# Module_Output_Sockets.net
KiCad netlist of a schematic drawn in Altium Designer
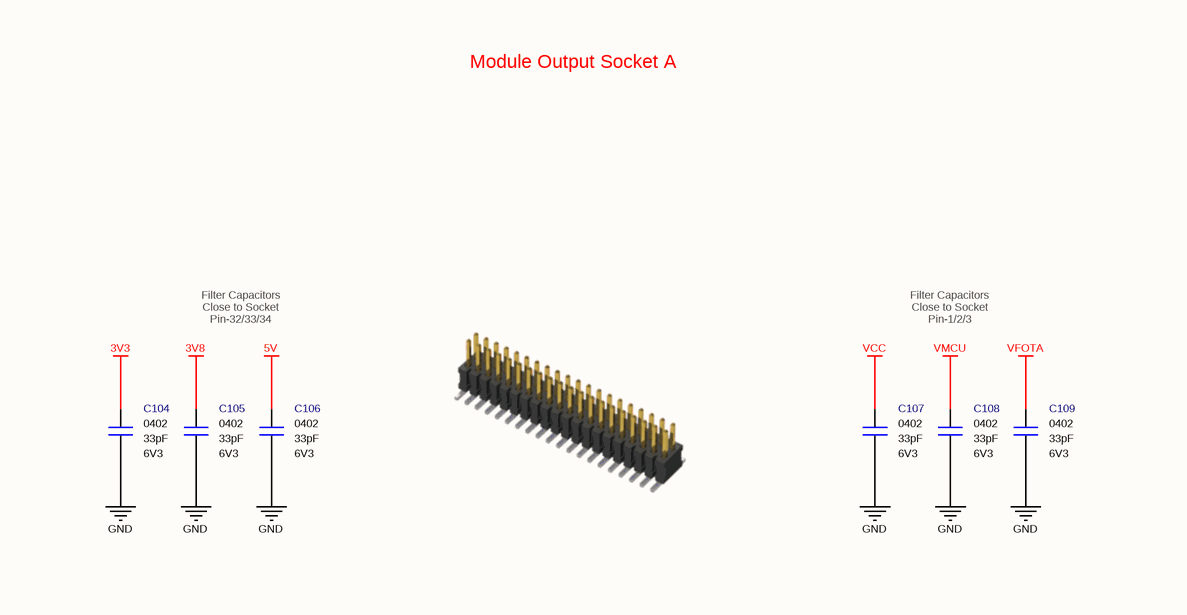
[diagram p0: Module Output Sockets.SchDoc, top left]
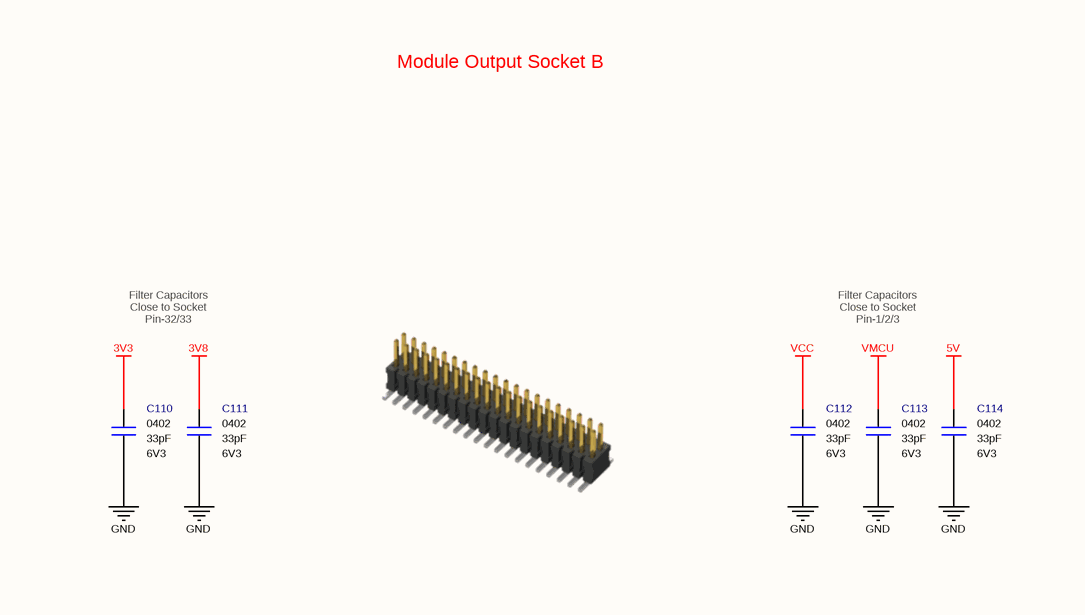
[diagram p1: Module Output Sockets.SchDoc, top right]
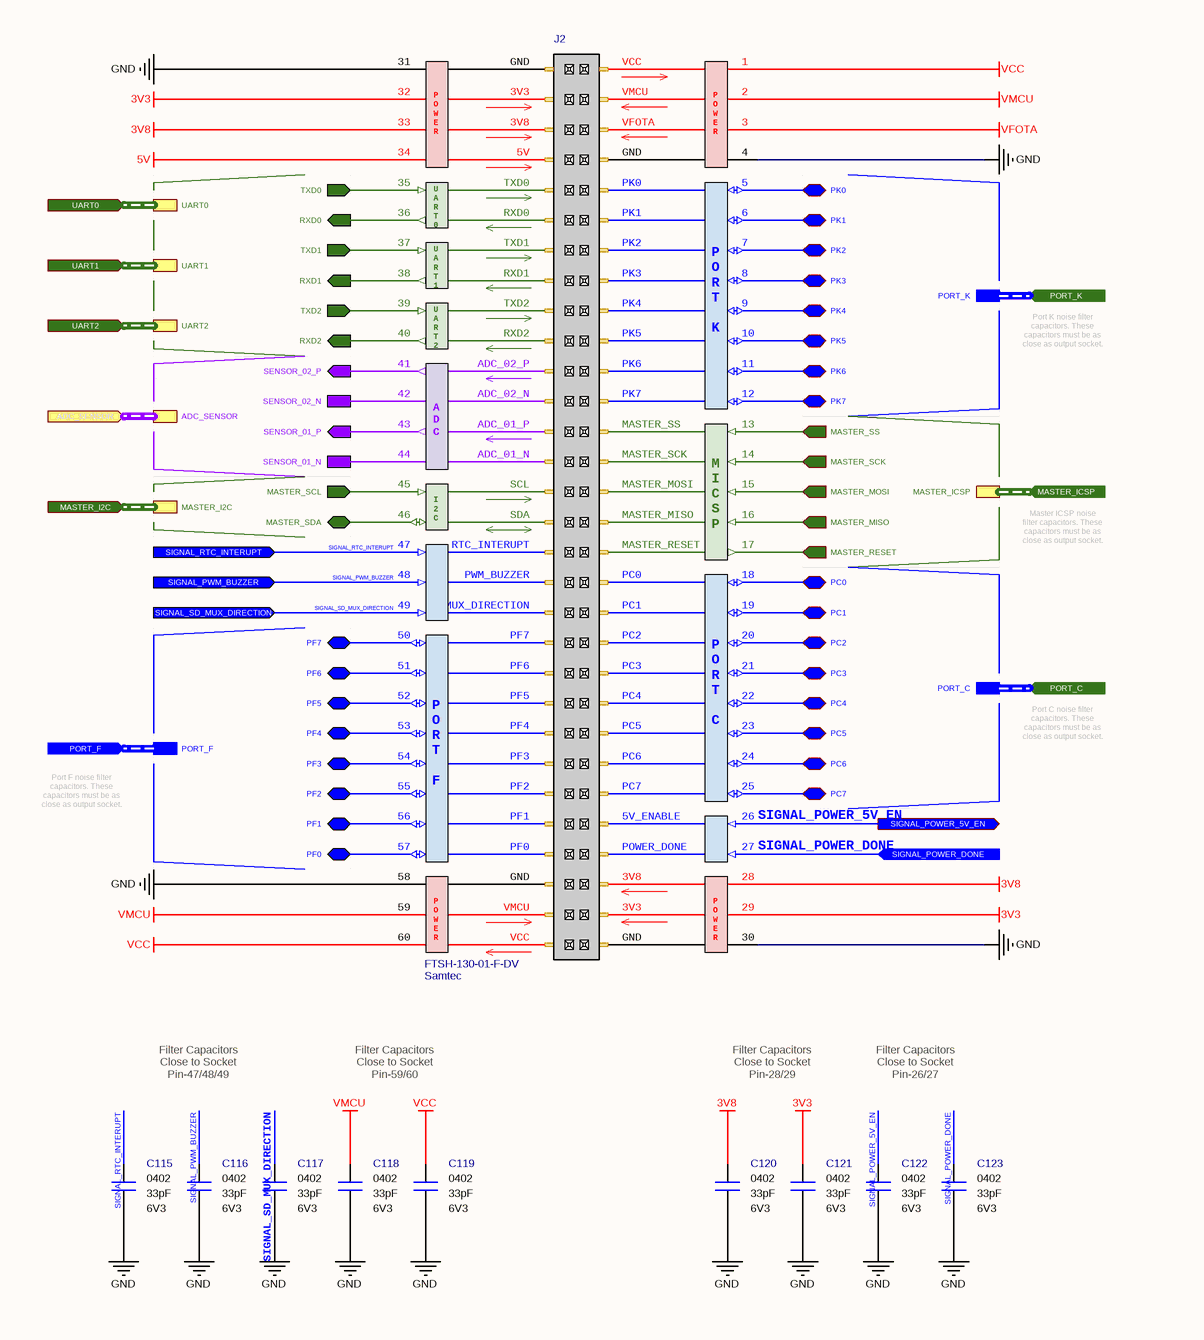
[diagram p2: Module Output Sockets.SchDoc, bottom left]
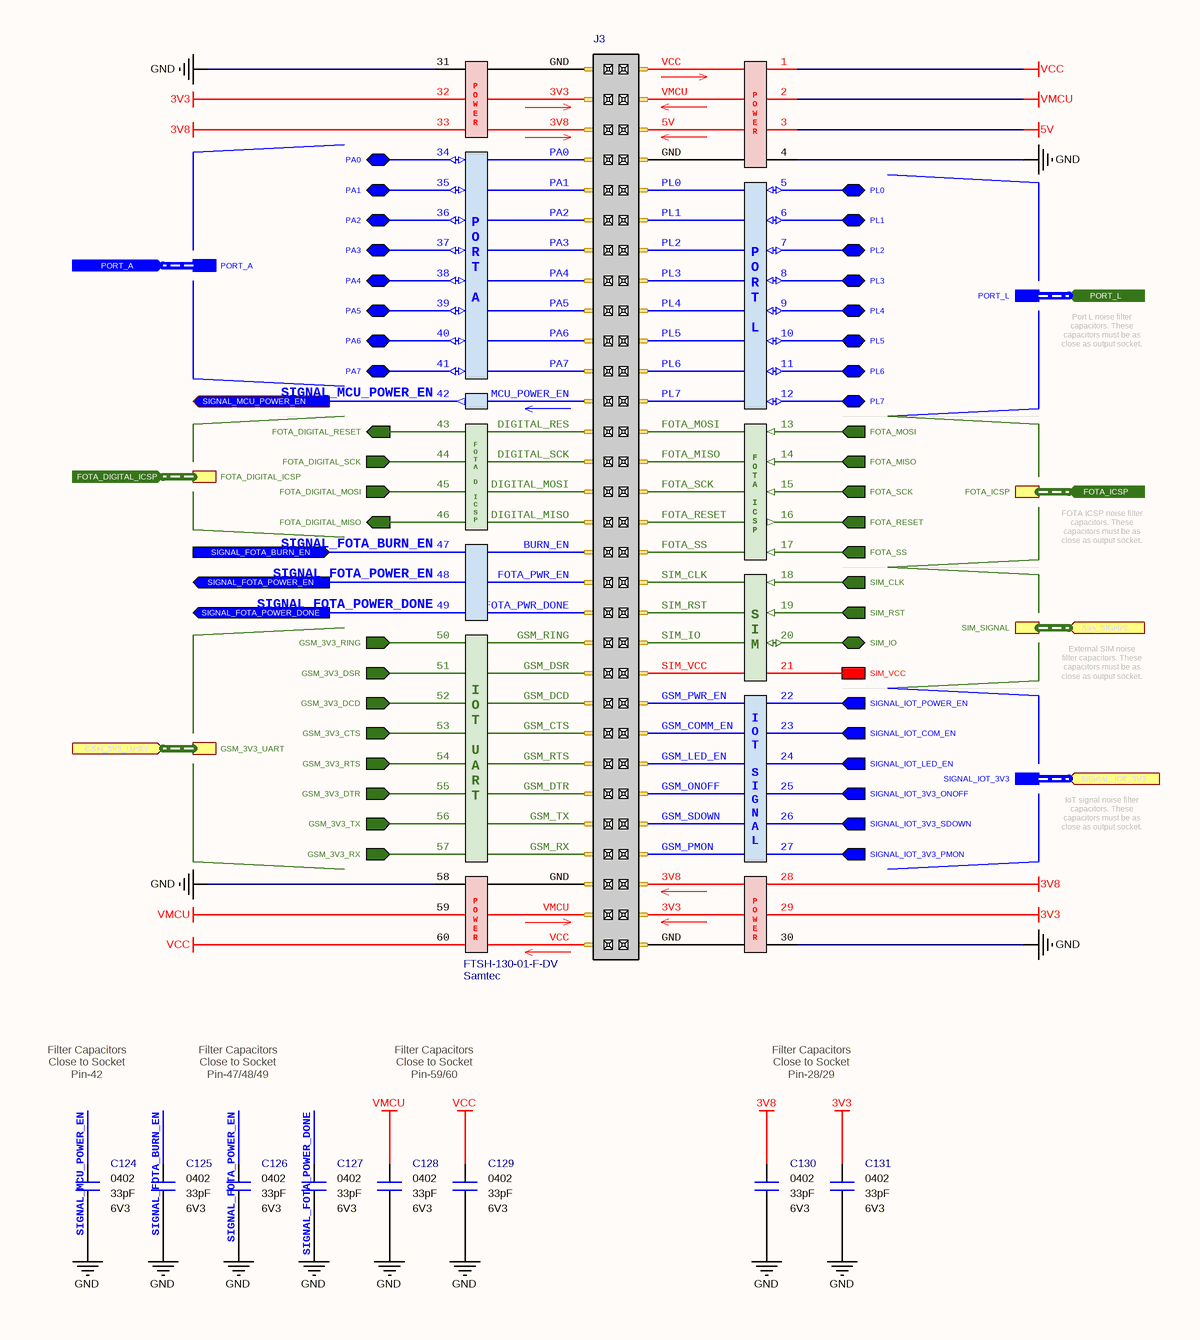
[diagram p3: Module Output Sockets.SchDoc, bottom right]

(export (version "E")
  (design (tool "Eeschema 10.0.6"))
  (components
    (comp (ref "C104")
      (value "33pF")
      (footprint "CAPACITOR_0402")
      (description "Capacitor - 33pF [0402] (Ceramic)")
      (fields
        (field (name "TOLERANCE") "10%")
        (field (name "CASE") "0402")
        (field (name "VOLTAGE") "6V3")
        (field (name "MANUFACTURER PART NUMBER") "C0402C330J9RACAUTO")
      )
      (libsource (lib "Ovoo_Library") (part "Capacitor - 33pF [0402-6V3]"))
    )
    (comp (ref "C105")
      (value "33pF")
      (footprint "CAPACITOR_0402")
      (description "Capacitor - 33pF [0402] (Ceramic)")
      (fields
        (field (name "TOLERANCE") "10%")
        (field (name "CASE") "0402")
        (field (name "VOLTAGE") "6V3")
        (field (name "MANUFACTURER PART NUMBER") "C0402C330J9RACAUTO")
      )
      (libsource (lib "Ovoo_Library") (part "Capacitor - 33pF [0402-6V3]"))
    )
    (comp (ref "C106")
      (value "33pF")
      (footprint "CAPACITOR_0402")
      (description "Capacitor - 33pF [0402] (Ceramic)")
      (fields
        (field (name "TOLERANCE") "10%")
        (field (name "CASE") "0402")
        (field (name "VOLTAGE") "6V3")
        (field (name "MANUFACTURER PART NUMBER") "C0402C330J9RACAUTO")
      )
      (libsource (lib "Ovoo_Library") (part "Capacitor - 33pF [0402-6V3]"))
    )
    (comp (ref "C107")
      (value "33pF")
      (footprint "CAPACITOR_0402")
      (description "Capacitor - 33pF [0402] (Ceramic)")
      (fields
        (field (name "TOLERANCE") "10%")
        (field (name "CASE") "0402")
        (field (name "VOLTAGE") "6V3")
        (field (name "MANUFACTURER PART NUMBER") "C0402C330J9RACAUTO")
      )
      (libsource (lib "Ovoo_Library") (part "Capacitor - 33pF [0402-6V3]"))
    )
    (comp (ref "C108")
      (value "33pF")
      (footprint "CAPACITOR_0402")
      (description "Capacitor - 33pF [0402] (Ceramic)")
      (fields
        (field (name "TOLERANCE") "10%")
        (field (name "CASE") "0402")
        (field (name "VOLTAGE") "6V3")
        (field (name "MANUFACTURER PART NUMBER") "C0402C330J9RACAUTO")
      )
      (libsource (lib "Ovoo_Library") (part "Capacitor - 33pF [0402-6V3]"))
    )
    (comp (ref "C109")
      (value "33pF")
      (footprint "CAPACITOR_0402")
      (description "Capacitor - 33pF [0402] (Ceramic)")
      (fields
        (field (name "TOLERANCE") "10%")
        (field (name "CASE") "0402")
        (field (name "VOLTAGE") "6V3")
        (field (name "MANUFACTURER PART NUMBER") "C0402C330J9RACAUTO")
      )
      (libsource (lib "Ovoo_Library") (part "Capacitor - 33pF [0402-6V3]"))
    )
    (comp (ref "C110")
      (value "33pF")
      (footprint "CAPACITOR_0402")
      (description "Capacitor - 33pF [0402] (Ceramic)")
      (fields
        (field (name "TOLERANCE") "10%")
        (field (name "CASE") "0402")
        (field (name "VOLTAGE") "6V3")
        (field (name "MANUFACTURER PART NUMBER") "C0402C330J9RACAUTO")
      )
      (libsource (lib "Ovoo_Library") (part "Capacitor - 33pF [0402-6V3]"))
    )
    (comp (ref "C111")
      (value "33pF")
      (footprint "CAPACITOR_0402")
      (description "Capacitor - 33pF [0402] (Ceramic)")
      (fields
        (field (name "TOLERANCE") "10%")
        (field (name "CASE") "0402")
        (field (name "VOLTAGE") "6V3")
        (field (name "MANUFACTURER PART NUMBER") "C0402C330J9RACAUTO")
      )
      (libsource (lib "Ovoo_Library") (part "Capacitor - 33pF [0402-6V3]"))
    )
    (comp (ref "C112")
      (value "33pF")
      (footprint "CAPACITOR_0402")
      (description "Capacitor - 33pF [0402] (Ceramic)")
      (fields
        (field (name "TOLERANCE") "10%")
        (field (name "CASE") "0402")
        (field (name "VOLTAGE") "6V3")
        (field (name "MANUFACTURER PART NUMBER") "C0402C330J9RACAUTO")
      )
      (libsource (lib "Ovoo_Library") (part "Capacitor - 33pF [0402-6V3]"))
    )
    (comp (ref "C113")
      (value "33pF")
      (footprint "CAPACITOR_0402")
      (description "Capacitor - 33pF [0402] (Ceramic)")
      (fields
        (field (name "TOLERANCE") "10%")
        (field (name "CASE") "0402")
        (field (name "VOLTAGE") "6V3")
        (field (name "MANUFACTURER PART NUMBER") "C0402C330J9RACAUTO")
      )
      (libsource (lib "Ovoo_Library") (part "Capacitor - 33pF [0402-6V3]"))
    )
    (comp (ref "C114")
      (value "33pF")
      (footprint "CAPACITOR_0402")
      (description "Capacitor - 33pF [0402] (Ceramic)")
      (fields
        (field (name "TOLERANCE") "10%")
        (field (name "CASE") "0402")
        (field (name "VOLTAGE") "6V3")
        (field (name "MANUFACTURER PART NUMBER") "C0402C330J9RACAUTO")
      )
      (libsource (lib "Ovoo_Library") (part "Capacitor - 33pF [0402-6V3]"))
    )
    (comp (ref "C115")
      (value "33pF")
      (footprint "CAPACITOR_0402")
      (description "Capacitor - 33pF [0402] (Ceramic)")
      (fields
        (field (name "TOLERANCE") "10%")
        (field (name "CASE") "0402")
        (field (name "VOLTAGE") "6V3")
        (field (name "MANUFACTURER PART NUMBER") "C0402C330J9RACAUTO")
      )
      (libsource (lib "Ovoo_Library") (part "Capacitor - 33pF [0402-6V3]"))
    )
    (comp (ref "C116")
      (value "33pF")
      (footprint "CAPACITOR_0402")
      (description "Capacitor - 33pF [0402] (Ceramic)")
      (fields
        (field (name "TOLERANCE") "10%")
        (field (name "CASE") "0402")
        (field (name "VOLTAGE") "6V3")
        (field (name "MANUFACTURER PART NUMBER") "C0402C330J9RACAUTO")
      )
      (libsource (lib "Ovoo_Library") (part "Capacitor - 33pF [0402-6V3]"))
    )
    (comp (ref "C117")
      (value "33pF")
      (footprint "CAPACITOR_0402")
      (description "Capacitor - 33pF [0402] (Ceramic)")
      (fields
        (field (name "TOLERANCE") "10%")
        (field (name "CASE") "0402")
        (field (name "VOLTAGE") "6V3")
        (field (name "MANUFACTURER PART NUMBER") "C0402C330J9RACAUTO")
      )
      (libsource (lib "Ovoo_Library") (part "Capacitor - 33pF [0402-6V3]"))
    )
    (comp (ref "C118")
      (value "33pF")
      (footprint "CAPACITOR_0402")
      (description "Capacitor - 33pF [0402] (Ceramic)")
      (fields
        (field (name "TOLERANCE") "10%")
        (field (name "CASE") "0402")
        (field (name "VOLTAGE") "6V3")
        (field (name "MANUFACTURER PART NUMBER") "C0402C330J9RACAUTO")
      )
      (libsource (lib "Ovoo_Library") (part "Capacitor - 33pF [0402-6V3]"))
    )
    (comp (ref "C119")
      (value "33pF")
      (footprint "CAPACITOR_0402")
      (description "Capacitor - 33pF [0402] (Ceramic)")
      (fields
        (field (name "TOLERANCE") "10%")
        (field (name "CASE") "0402")
        (field (name "VOLTAGE") "6V3")
        (field (name "MANUFACTURER PART NUMBER") "C0402C330J9RACAUTO")
      )
      (libsource (lib "Ovoo_Library") (part "Capacitor - 33pF [0402-6V3]"))
    )
    (comp (ref "C120")
      (value "33pF")
      (footprint "CAPACITOR_0402")
      (description "Capacitor - 33pF [0402] (Ceramic)")
      (fields
        (field (name "TOLERANCE") "10%")
        (field (name "CASE") "0402")
        (field (name "VOLTAGE") "6V3")
        (field (name "MANUFACTURER PART NUMBER") "C0402C330J9RACAUTO")
      )
      (libsource (lib "Ovoo_Library") (part "Capacitor - 33pF [0402-6V3]"))
    )
    (comp (ref "C121")
      (value "33pF")
      (footprint "CAPACITOR_0402")
      (description "Capacitor - 33pF [0402] (Ceramic)")
      (fields
        (field (name "TOLERANCE") "10%")
        (field (name "CASE") "0402")
        (field (name "VOLTAGE") "6V3")
        (field (name "MANUFACTURER PART NUMBER") "C0402C330J9RACAUTO")
      )
      (libsource (lib "Ovoo_Library") (part "Capacitor - 33pF [0402-6V3]"))
    )
    (comp (ref "C122")
      (value "33pF")
      (footprint "CAPACITOR_0402")
      (description "Capacitor - 33pF [0402] (Ceramic)")
      (fields
        (field (name "TOLERANCE") "10%")
        (field (name "CASE") "0402")
        (field (name "VOLTAGE") "6V3")
        (field (name "MANUFACTURER PART NUMBER") "C0402C330J9RACAUTO")
      )
      (libsource (lib "Ovoo_Library") (part "Capacitor - 33pF [0402-6V3]"))
    )
    (comp (ref "C123")
      (value "33pF")
      (footprint "CAPACITOR_0402")
      (description "Capacitor - 33pF [0402] (Ceramic)")
      (fields
        (field (name "TOLERANCE") "10%")
        (field (name "CASE") "0402")
        (field (name "VOLTAGE") "6V3")
        (field (name "MANUFACTURER PART NUMBER") "C0402C330J9RACAUTO")
      )
      (libsource (lib "Ovoo_Library") (part "Capacitor - 33pF [0402-6V3]"))
    )
    (comp (ref "C124")
      (value "33pF")
      (footprint "CAPACITOR_0402")
      (description "Capacitor - 33pF [0402] (Ceramic)")
      (fields
        (field (name "TOLERANCE") "10%")
        (field (name "CASE") "0402")
        (field (name "VOLTAGE") "6V3")
        (field (name "MANUFACTURER PART NUMBER") "C0402C330J9RACAUTO")
      )
      (libsource (lib "Ovoo_Library") (part "Capacitor - 33pF [0402-6V3]"))
    )
    (comp (ref "C125")
      (value "33pF")
      (footprint "CAPACITOR_0402")
      (description "Capacitor - 33pF [0402] (Ceramic)")
      (fields
        (field (name "TOLERANCE") "10%")
        (field (name "CASE") "0402")
        (field (name "VOLTAGE") "6V3")
        (field (name "MANUFACTURER PART NUMBER") "C0402C330J9RACAUTO")
      )
      (libsource (lib "Ovoo_Library") (part "Capacitor - 33pF [0402-6V3]"))
    )
    (comp (ref "C126")
      (value "33pF")
      (footprint "CAPACITOR_0402")
      (description "Capacitor - 33pF [0402] (Ceramic)")
      (fields
        (field (name "TOLERANCE") "10%")
        (field (name "CASE") "0402")
        (field (name "VOLTAGE") "6V3")
        (field (name "MANUFACTURER PART NUMBER") "C0402C330J9RACAUTO")
      )
      (libsource (lib "Ovoo_Library") (part "Capacitor - 33pF [0402-6V3]"))
    )
    (comp (ref "C127")
      (value "33pF")
      (footprint "CAPACITOR_0402")
      (description "Capacitor - 33pF [0402] (Ceramic)")
      (fields
        (field (name "TOLERANCE") "10%")
        (field (name "CASE") "0402")
        (field (name "VOLTAGE") "6V3")
        (field (name "MANUFACTURER PART NUMBER") "C0402C330J9RACAUTO")
      )
      (libsource (lib "Ovoo_Library") (part "Capacitor - 33pF [0402-6V3]"))
    )
    (comp (ref "C128")
      (value "33pF")
      (footprint "CAPACITOR_0402")
      (description "Capacitor - 33pF [0402] (Ceramic)")
      (fields
        (field (name "TOLERANCE") "10%")
        (field (name "CASE") "0402")
        (field (name "VOLTAGE") "6V3")
        (field (name "MANUFACTURER PART NUMBER") "C0402C330J9RACAUTO")
      )
      (libsource (lib "Ovoo_Library") (part "Capacitor - 33pF [0402-6V3]"))
    )
    (comp (ref "C129")
      (value "33pF")
      (footprint "CAPACITOR_0402")
      (description "Capacitor - 33pF [0402] (Ceramic)")
      (fields
        (field (name "TOLERANCE") "10%")
        (field (name "CASE") "0402")
        (field (name "VOLTAGE") "6V3")
        (field (name "MANUFACTURER PART NUMBER") "C0402C330J9RACAUTO")
      )
      (libsource (lib "Ovoo_Library") (part "Capacitor - 33pF [0402-6V3]"))
    )
    (comp (ref "C130")
      (value "33pF")
      (footprint "CAPACITOR_0402")
      (description "Capacitor - 33pF [0402] (Ceramic)")
      (fields
        (field (name "TOLERANCE") "10%")
        (field (name "CASE") "0402")
        (field (name "VOLTAGE") "6V3")
        (field (name "MANUFACTURER PART NUMBER") "C0402C330J9RACAUTO")
      )
      (libsource (lib "Ovoo_Library") (part "Capacitor - 33pF [0402-6V3]"))
    )
    (comp (ref "C131")
      (value "33pF")
      (footprint "CAPACITOR_0402")
      (description "Capacitor - 33pF [0402] (Ceramic)")
      (fields
        (field (name "TOLERANCE") "10%")
        (field (name "CASE") "0402")
        (field (name "VOLTAGE") "6V3")
        (field (name "MANUFACTURER PART NUMBER") "C0402C330J9RACAUTO")
      )
      (libsource (lib "Ovoo_Library") (part "Capacitor - 33pF [0402-6V3]"))
    )
    (comp (ref "J2")
      (value "1.27 mm Pitch 2x30P Male Connector")
      (footprint "SAMTEC-FTSH-130-01-X-DV")
      (description "Headers & Wire Housings BREAKAWAY HDR VERT 6")
      (fields
        (field (name "MOUSER PART NUMBER") "200-FTSH13001FDV")
        (field (name "MANUFACTURER PART NUMBER") "FTSH-130-01-F-DV")
        (field (name "MANUFACTURER NAME") "Samtec")
      )
      (libsource (lib "Ovoo_Library") (part "Connector - B100 Male Socket [A]"))
    )
    (comp (ref "J3")
      (value "1.27 mm Pitch 2x30P Male Connector")
      (footprint "SAMTEC-FTSH-130-01-X-DV")
      (description "Headers & Wire Housings BREAKAWAY HDR VERT 6")
      (fields
        (field (name "MOUSER PART NUMBER") "200-FTSH13001FDV")
        (field (name "MANUFACTURER PART NUMBER") "FTSH-130-01-F-DV")
        (field (name "MANUFACTURER NAME") "Samtec")
      )
      (libsource (lib "Ovoo_Library") (part "Connector - B100 Male Socket [B]"))
    )
  )
  (nets
    (net (code "19") (name "/FOTA_DIGITAL_MISO") (class "Default")
      (node (ref "J3") (pin "46") (pinfunction "Pin-46_46") (pintype "passive"))
    )
    (net (code "20") (name "/FOTA_DIGITAL_MOSI") (class "Default")
      (node (ref "J3") (pin "45") (pinfunction "Pin-45_45") (pintype "passive"))
    )
    (net (code "21") (name "/FOTA_DIGITAL_RESET") (class "Default")
      (node (ref "J3") (pin "43") (pinfunction "Pin-43_43") (pintype "passive"))
    )
    (net (code "22") (name "/FOTA_DIGITAL_SCK") (class "Default")
      (node (ref "J3") (pin "44") (pinfunction "Pin-44_44") (pintype "passive"))
    )
    (net (code "24") (name "/FOTA_MISO") (class "Default")
      (node (ref "J3") (pin "14") (pinfunction "Pin-14_14") (pintype "input"))
    )
    (net (code "25") (name "/FOTA_MOSI") (class "Default")
      (node (ref "J3") (pin "13") (pinfunction "Pin-13_13") (pintype "input"))
    )
    (net (code "26") (name "/FOTA_RESET") (class "Default")
      (node (ref "J3") (pin "16") (pinfunction "Pin-16_16") (pintype "output"))
    )
    (net (code "27") (name "/FOTA_SCK") (class "Default")
      (node (ref "J3") (pin "15") (pinfunction "Pin-15_15") (pintype "input"))
    )
    (net (code "28") (name "/FOTA_SS") (class "Default")
      (node (ref "J3") (pin "17") (pinfunction "Pin-17_17") (pintype "input"))
    )
    (net (code "29") (name "/GSM_3V3_CTS") (class "Default")
      (node (ref "J3") (pin "53") (pinfunction "Pin-53_53") (pintype "passive"))
    )
    (net (code "30") (name "/GSM_3V3_DCD") (class "Default")
      (node (ref "J3") (pin "52") (pinfunction "Pin-52_52") (pintype "passive"))
    )
    (net (code "31") (name "/GSM_3V3_DSR") (class "Default")
      (node (ref "J3") (pin "51") (pinfunction "Pin-51_51") (pintype "passive"))
    )
    (net (code "32") (name "/GSM_3V3_DTR") (class "Default")
      (node (ref "J3") (pin "55") (pinfunction "Pin-55_55") (pintype "passive"))
    )
    (net (code "33") (name "/GSM_3V3_RING") (class "Default")
      (node (ref "J3") (pin "50") (pinfunction "Pin-50_50") (pintype "passive"))
    )
    (net (code "34") (name "/GSM_3V3_RTS") (class "Default")
      (node (ref "J3") (pin "54") (pinfunction "Pin-54_54") (pintype "passive"))
    )
    (net (code "35") (name "/GSM_3V3_RX") (class "Default")
      (node (ref "J3") (pin "57") (pinfunction "Pin-57_57") (pintype "passive"))
    )
    (net (code "36") (name "/GSM_3V3_TX") (class "Default")
      (node (ref "J3") (pin "56") (pinfunction "Pin-56_56") (pintype "passive"))
    )
    (net (code "40") (name "/MASTER_MISO") (class "Default")
      (node (ref "J2") (pin "16") (pinfunction "Pin-16_16") (pintype "input"))
    )
    (net (code "41") (name "/MASTER_MOSI") (class "Default")
      (node (ref "J2") (pin "15") (pinfunction "Pin-15_15") (pintype "input"))
    )
    (net (code "42") (name "/MASTER_RESET") (class "Default")
      (node (ref "J2") (pin "17") (pinfunction "Pin-17_17") (pintype "output"))
    )
    (net (code "43") (name "/MASTER_SCK") (class "Default")
      (node (ref "J2") (pin "14") (pinfunction "Pin-14_14") (pintype "input"))
    )
    (net (code "44") (name "/MASTER_SCL") (class "Default")
      (node (ref "J2") (pin "45") (pinfunction "Pin-45_45") (pintype "input"))
    )
    (net (code "45") (name "/MASTER_SDA") (class "Default")
      (node (ref "J2") (pin "46") (pinfunction "Pin-46_46") (pintype "bidirectional"))
    )
    (net (code "46") (name "/MASTER_SS") (class "Default")
      (node (ref "J2") (pin "13") (pinfunction "Pin-13_13") (pintype "input"))
    )
    (net (code "47") (name "/PA0") (class "Default")
      (node (ref "J3") (pin "34") (pinfunction "Pin-34_34") (pintype "bidirectional"))
    )
    (net (code "48") (name "/PA1") (class "Default")
      (node (ref "J3") (pin "35") (pinfunction "Pin-35_35") (pintype "bidirectional"))
    )
    (net (code "49") (name "/PA2") (class "Default")
      (node (ref "J3") (pin "36") (pinfunction "Pin-36_36") (pintype "bidirectional"))
    )
    (net (code "50") (name "/PA3") (class "Default")
      (node (ref "J3") (pin "37") (pinfunction "Pin-37_37") (pintype "bidirectional"))
    )
    (net (code "51") (name "/PA4") (class "Default")
      (node (ref "J3") (pin "38") (pinfunction "Pin-38_38") (pintype "bidirectional"))
    )
    (net (code "52") (name "/PA5") (class "Default")
      (node (ref "J3") (pin "39") (pinfunction "Pin-39_39") (pintype "bidirectional"))
    )
    (net (code "53") (name "/PA6") (class "Default")
      (node (ref "J3") (pin "40") (pinfunction "Pin-40_40") (pintype "bidirectional"))
    )
    (net (code "54") (name "/PA7") (class "Default")
      (node (ref "J3") (pin "41") (pinfunction "Pin-41_41") (pintype "bidirectional"))
    )
    (net (code "55") (name "/PC0") (class "Default")
      (node (ref "J2") (pin "18") (pinfunction "Pin-18_18") (pintype "bidirectional"))
    )
    (net (code "56") (name "/PC1") (class "Default")
      (node (ref "J2") (pin "19") (pinfunction "Pin-19_19") (pintype "bidirectional"))
    )
    (net (code "57") (name "/PC2") (class "Default")
      (node (ref "J2") (pin "20") (pinfunction "Pin-20_20") (pintype "bidirectional"))
    )
    (net (code "58") (name "/PC3") (class "Default")
      (node (ref "J2") (pin "21") (pinfunction "Pin-21_21") (pintype "bidirectional"))
    )
    (net (code "59") (name "/PC4") (class "Default")
      (node (ref "J2") (pin "22") (pinfunction "Pin-22_22") (pintype "bidirectional"))
    )
    (net (code "60") (name "/PC5") (class "Default")
      (node (ref "J2") (pin "23") (pinfunction "Pin-23_23") (pintype "bidirectional"))
    )
    (net (code "61") (name "/PC6") (class "Default")
      (node (ref "J2") (pin "24") (pinfunction "Pin-24_24") (pintype "bidirectional"))
    )
    (net (code "62") (name "/PC7") (class "Default")
      (node (ref "J2") (pin "25") (pinfunction "Pin-25_25") (pintype "bidirectional"))
    )
    (net (code "63") (name "/PF0") (class "Default")
      (node (ref "J2") (pin "57") (pinfunction "Pin-57_57") (pintype "bidirectional"))
    )
    (net (code "64") (name "/PF1") (class "Default")
      (node (ref "J2") (pin "56") (pinfunction "Pin-56_56") (pintype "bidirectional"))
    )
    (net (code "65") (name "/PF2") (class "Default")
      (node (ref "J2") (pin "55") (pinfunction "Pin-55_55") (pintype "bidirectional"))
    )
    (net (code "66") (name "/PF3") (class "Default")
      (node (ref "J2") (pin "54") (pinfunction "Pin-54_54") (pintype "bidirectional"))
    )
    (net (code "67") (name "/PF4") (class "Default")
      (node (ref "J2") (pin "53") (pinfunction "Pin-53_53") (pintype "bidirectional"))
    )
    (net (code "68") (name "/PF5") (class "Default")
      (node (ref "J2") (pin "52") (pinfunction "Pin-52_52") (pintype "bidirectional"))
    )
    (net (code "69") (name "/PF6") (class "Default")
      (node (ref "J2") (pin "51") (pinfunction "Pin-51_51") (pintype "bidirectional"))
    )
    (net (code "70") (name "/PF7") (class "Default")
      (node (ref "J2") (pin "50") (pinfunction "Pin-50_50") (pintype "bidirectional"))
    )
    (net (code "71") (name "/PK0") (class "Default")
      (node (ref "J2") (pin "5") (pinfunction "Pin-5_5") (pintype "bidirectional"))
    )
    (net (code "72") (name "/PK1") (class "Default")
      (node (ref "J2") (pin "6") (pinfunction "Pin-6_6") (pintype "bidirectional"))
    )
    (net (code "73") (name "/PK2") (class "Default")
      (node (ref "J2") (pin "7") (pinfunction "Pin-7_7") (pintype "bidirectional"))
    )
    (net (code "74") (name "/PK3") (class "Default")
      (node (ref "J2") (pin "8") (pinfunction "Pin-8_8") (pintype "bidirectional"))
    )
    (net (code "75") (name "/PK4") (class "Default")
      (node (ref "J2") (pin "9") (pinfunction "Pin-9_9") (pintype "bidirectional"))
    )
    (net (code "76") (name "/PK5") (class "Default")
      (node (ref "J2") (pin "10") (pinfunction "Pin-10_10") (pintype "bidirectional"))
    )
    (net (code "77") (name "/PK6") (class "Default")
      (node (ref "J2") (pin "11") (pinfunction "Pin-11_11") (pintype "bidirectional"))
    )
    (net (code "78") (name "/PK7") (class "Default")
      (node (ref "J2") (pin "12") (pinfunction "Pin-12_12") (pintype "bidirectional"))
    )
    (net (code "79") (name "/PL0") (class "Default")
      (node (ref "J3") (pin "5") (pinfunction "Pin-5_5") (pintype "bidirectional"))
    )
    (net (code "80") (name "/PL1") (class "Default")
      (node (ref "J3") (pin "6") (pinfunction "Pin-6_6") (pintype "bidirectional"))
    )
    (net (code "81") (name "/PL2") (class "Default")
      (node (ref "J3") (pin "7") (pinfunction "Pin-7_7") (pintype "bidirectional"))
    )
    (net (code "82") (name "/PL3") (class "Default")
      (node (ref "J3") (pin "8") (pinfunction "Pin-8_8") (pintype "bidirectional"))
    )
    (net (code "83") (name "/PL4") (class "Default")
      (node (ref "J3") (pin "9") (pinfunction "Pin-9_9") (pintype "bidirectional"))
    )
    (net (code "84") (name "/PL5") (class "Default")
      (node (ref "J3") (pin "10") (pinfunction "Pin-10_10") (pintype "bidirectional"))
    )
    (net (code "85") (name "/PL6") (class "Default")
      (node (ref "J3") (pin "11") (pinfunction "Pin-11_11") (pintype "bidirectional"))
    )
    (net (code "86") (name "/PL7") (class "Default")
      (node (ref "J3") (pin "12") (pinfunction "Pin-12_12") (pintype "bidirectional"))
    )
    (net (code "92") (name "/RXD0") (class "Default")
      (node (ref "J2") (pin "36") (pinfunction "Pin-36_36") (pintype "output"))
    )
    (net (code "93") (name "/RXD1") (class "Default")
      (node (ref "J2") (pin "38") (pinfunction "Pin-38_38") (pintype "output"))
    )
    (net (code "94") (name "/RXD2") (class "Default")
      (node (ref "J2") (pin "40") (pinfunction "Pin-40_40") (pintype "output"))
    )
    (net (code "95") (name "/SENSOR_01_N") (class "Default")
      (node (ref "J2") (pin "44") (pinfunction "Pin-44_44") (pintype "passive"))
    )
    (net (code "96") (name "/SENSOR_01_P") (class "Default")
      (node (ref "J2") (pin "43") (pinfunction "Pin-43_43") (pintype "output"))
    )
    (net (code "97") (name "/SENSOR_02_N") (class "Default")
      (node (ref "J2") (pin "42") (pinfunction "Pin-42_42") (pintype "passive"))
    )
    (net (code "98") (name "/SENSOR_02_P") (class "Default")
      (node (ref "J2") (pin "41") (pinfunction "Pin-41_41") (pintype "output"))
    )
    (net (code "99") (name "/SIGNAL_FOTA_BURN_EN") (class "Default")
      (node (ref "C125") (pin "2") (pinfunction "2_2") (pintype "passive"))
      (node (ref "J3") (pin "47") (pinfunction "Pin-47_47") (pintype "passive"))
    )
    (net (code "100") (name "/SIGNAL_FOTA_POWER_DONE") (class "Default")
      (node (ref "C127") (pin "2") (pinfunction "2_2") (pintype "passive"))
      (node (ref "J3") (pin "49") (pinfunction "Pin-49_49") (pintype "passive"))
    )
    (net (code "101") (name "/SIGNAL_FOTA_POWER_EN") (class "Default")
      (node (ref "C126") (pin "2") (pinfunction "2_2") (pintype "passive"))
      (node (ref "J3") (pin "48") (pinfunction "Pin-48_48") (pintype "passive"))
    )
    (net (code "102") (name "/SIGNAL_IOT_3V3_ONOFF") (class "Default")
      (node (ref "J3") (pin "25") (pinfunction "Pin-25_25") (pintype "passive"))
    )
    (net (code "103") (name "/SIGNAL_IOT_3V3_PMON") (class "Default")
      (node (ref "J3") (pin "27") (pinfunction "Pin-27_27") (pintype "passive"))
    )
    (net (code "104") (name "/SIGNAL_IOT_3V3_SDOWN") (class "Default")
      (node (ref "J3") (pin "26") (pinfunction "Pin-26_26") (pintype "passive"))
    )
    (net (code "106") (name "/SIGNAL_IOT_COM_EN") (class "Default")
      (node (ref "J3") (pin "23") (pinfunction "Pin-23_23") (pintype "passive"))
    )
    (net (code "107") (name "/SIGNAL_IOT_LED_EN") (class "Default")
      (node (ref "J3") (pin "24") (pinfunction "Pin-24_24") (pintype "passive"))
    )
    (net (code "108") (name "/SIGNAL_IOT_POWER_EN") (class "Default")
      (node (ref "J3") (pin "22") (pinfunction "Pin-22_22") (pintype "passive"))
    )
    (net (code "109") (name "/SIGNAL_MCU_POWER_EN") (class "Default")
      (node (ref "C124") (pin "2") (pinfunction "2_2") (pintype "passive"))
      (node (ref "J3") (pin "42") (pinfunction "Pin-42_42") (pintype "output"))
    )
    (net (code "110") (name "/SIGNAL_POWER_5V_EN") (class "Default")
      (node (ref "C122") (pin "2") (pinfunction "2_2") (pintype "passive"))
      (node (ref "J2") (pin "26") (pinfunction "Pin-26_26") (pintype "input"))
    )
    (net (code "111") (name "/SIGNAL_POWER_DONE") (class "Default")
      (node (ref "C123") (pin "2") (pinfunction "2_2") (pintype "passive"))
      (node (ref "J2") (pin "27") (pinfunction "Pin-27_27") (pintype "input"))
    )
    (net (code "112") (name "/SIGNAL_PWM_BUZZER") (class "Default")
      (node (ref "C116") (pin "2") (pinfunction "2_2") (pintype "passive"))
      (node (ref "J2") (pin "48") (pinfunction "Pin-48_48") (pintype "input"))
    )
    (net (code "113") (name "/SIGNAL_RTC_INTERUPT") (class "Default")
      (node (ref "C115") (pin "2") (pinfunction "2_2") (pintype "passive"))
      (node (ref "J2") (pin "47") (pinfunction "Pin-47_47") (pintype "input"))
    )
    (net (code "114") (name "/SIGNAL_SD_MUX_DIRECTION") (class "Default")
      (node (ref "C117") (pin "2") (pinfunction "2_2") (pintype "passive"))
      (node (ref "J2") (pin "49") (pinfunction "Pin-49_49") (pintype "input"))
    )
    (net (code "115") (name "/SIM_CLK") (class "Default")
      (node (ref "J3") (pin "18") (pinfunction "Pin-18_18") (pintype "input"))
    )
    (net (code "116") (name "/SIM_IO") (class "Default")
      (node (ref "J3") (pin "20") (pinfunction "Pin-20_20") (pintype "bidirectional"))
    )
    (net (code "117") (name "/SIM_RST") (class "Default")
      (node (ref "J3") (pin "19") (pinfunction "Pin-19_19") (pintype "input"))
    )
    (net (code "119") (name "/SIM_VCC") (class "Default")
      (node (ref "J3") (pin "21") (pinfunction "Pin-21_21") (pintype "power_in"))
    )
    (net (code "120") (name "/TXD0") (class "Default")
      (node (ref "J2") (pin "35") (pinfunction "Pin-35_35") (pintype "input"))
    )
    (net (code "121") (name "/TXD1") (class "Default")
      (node (ref "J2") (pin "37") (pinfunction "Pin-37_37") (pintype "input"))
    )
    (net (code "122") (name "/TXD2") (class "Default")
      (node (ref "J2") (pin "39") (pinfunction "Pin-39_39") (pintype "input"))
    )
    (net (code "126") (name "3V3") (class "Default")
      (node (ref "C104") (pin "2") (pinfunction "2_2") (pintype "passive"))
      (node (ref "C110") (pin "2") (pinfunction "2_2") (pintype "passive"))
      (node (ref "C121") (pin "2") (pinfunction "2_2") (pintype "passive"))
      (node (ref "C131") (pin "2") (pinfunction "2_2") (pintype "passive"))
      (node (ref "J2") (pin "29") (pinfunction "Pin-29_29") (pintype "passive"))
      (node (ref "J2") (pin "32") (pinfunction "Pin-32_32") (pintype "power_in"))
      (node (ref "J3") (pin "29") (pinfunction "Pin-29_29") (pintype "power_in"))
      (node (ref "J3") (pin "32") (pinfunction "Pin-32_32") (pintype "power_in"))
    )
    (net (code "127") (name "3V8") (class "Default")
      (node (ref "C105") (pin "2") (pinfunction "2_2") (pintype "passive"))
      (node (ref "C111") (pin "2") (pinfunction "2_2") (pintype "passive"))
      (node (ref "C120") (pin "2") (pinfunction "2_2") (pintype "passive"))
      (node (ref "C130") (pin "2") (pinfunction "2_2") (pintype "passive"))
      (node (ref "J2") (pin "28") (pinfunction "Pin-28_28") (pintype "passive"))
      (node (ref "J2") (pin "33") (pinfunction "Pin-33_33") (pintype "power_in"))
      (node (ref "J3") (pin "28") (pinfunction "Pin-28_28") (pintype "power_in"))
      (node (ref "J3") (pin "33") (pinfunction "Pin-33_33") (pintype "power_in"))
    )
    (net (code "128") (name "5V") (class "Default")
      (node (ref "C106") (pin "2") (pinfunction "2_2") (pintype "passive"))
      (node (ref "C114") (pin "2") (pinfunction "2_2") (pintype "passive"))
      (node (ref "J2") (pin "34") (pinfunction "Pin-34_34") (pintype "power_in"))
      (node (ref "J3") (pin "3") (pinfunction "Pin-3_3") (pintype "power_in"))
    )
    (net (code "129") (name "GND") (class "Default")
      (node (ref "C104") (pin "1") (pinfunction "1_1") (pintype "passive"))
      (node (ref "C105") (pin "1") (pinfunction "1_1") (pintype "passive"))
      (node (ref "C106") (pin "1") (pinfunction "1_1") (pintype "passive"))
      (node (ref "C107") (pin "1") (pinfunction "1_1") (pintype "passive"))
      (node (ref "C108") (pin "1") (pinfunction "1_1") (pintype "passive"))
      (node (ref "C109") (pin "1") (pinfunction "1_1") (pintype "passive"))
      (node (ref "C110") (pin "1") (pinfunction "1_1") (pintype "passive"))
      (node (ref "C111") (pin "1") (pinfunction "1_1") (pintype "passive"))
      (node (ref "C112") (pin "1") (pinfunction "1_1") (pintype "passive"))
      (node (ref "C113") (pin "1") (pinfunction "1_1") (pintype "passive"))
      (node (ref "C114") (pin "1") (pinfunction "1_1") (pintype "passive"))
      (node (ref "C115") (pin "1") (pinfunction "1_1") (pintype "passive"))
      (node (ref "C116") (pin "1") (pinfunction "1_1") (pintype "passive"))
      (node (ref "C117") (pin "1") (pinfunction "1_1") (pintype "passive"))
      (node (ref "C118") (pin "1") (pinfunction "1_1") (pintype "passive"))
      (node (ref "C119") (pin "1") (pinfunction "1_1") (pintype "passive"))
      (node (ref "C120") (pin "1") (pinfunction "1_1") (pintype "passive"))
      (node (ref "C121") (pin "1") (pinfunction "1_1") (pintype "passive"))
      (node (ref "C122") (pin "1") (pinfunction "1_1") (pintype "passive"))
      (node (ref "C123") (pin "1") (pinfunction "1_1") (pintype "passive"))
      (node (ref "C124") (pin "1") (pinfunction "1_1") (pintype "passive"))
      (node (ref "C125") (pin "1") (pinfunction "1_1") (pintype "passive"))
      (node (ref "C126") (pin "1") (pinfunction "1_1") (pintype "passive"))
      (node (ref "C127") (pin "1") (pinfunction "1_1") (pintype "passive"))
      (node (ref "C128") (pin "1") (pinfunction "1_1") (pintype "passive"))
      (node (ref "C129") (pin "1") (pinfunction "1_1") (pintype "passive"))
      (node (ref "C130") (pin "1") (pinfunction "1_1") (pintype "passive"))
      (node (ref "C131") (pin "1") (pinfunction "1_1") (pintype "passive"))
      (node (ref "J2") (pin "30") (pinfunction "Pin-30_30") (pintype "passive"))
      (node (ref "J2") (pin "31") (pinfunction "Pin-31_31") (pintype "power_in"))
      (node (ref "J2") (pin "4") (pinfunction "Pin-4_4") (pintype "power_in"))
      (node (ref "J2") (pin "58") (pinfunction "Pin-58_58") (pintype "power_in"))
      (node (ref "J3") (pin "30") (pinfunction "Pin-30_30") (pintype "power_in"))
      (node (ref "J3") (pin "31") (pinfunction "Pin-31_31") (pintype "power_in"))
      (node (ref "J3") (pin "4") (pinfunction "Pin-4_4") (pintype "power_in"))
      (node (ref "J3") (pin "58") (pinfunction "Pin-58_58") (pintype "power_in"))
    )
    (net (code "130") (name "VCC") (class "Default")
      (node (ref "C107") (pin "2") (pinfunction "2_2") (pintype "passive"))
      (node (ref "C112") (pin "2") (pinfunction "2_2") (pintype "passive"))
      (node (ref "C119") (pin "2") (pinfunction "2_2") (pintype "passive"))
      (node (ref "C129") (pin "2") (pinfunction "2_2") (pintype "passive"))
      (node (ref "J2") (pin "1") (pinfunction "Pin-1_1") (pintype "power_in"))
      (node (ref "J2") (pin "60") (pinfunction "Pin-60_60") (pintype "power_in"))
      (node (ref "J3") (pin "1") (pinfunction "Pin-1_1") (pintype "power_in"))
      (node (ref "J3") (pin "60") (pinfunction "Pin-60_60") (pintype "power_in"))
    )
    (net (code "131") (name "VFOTA") (class "Default")
      (node (ref "C109") (pin "2") (pinfunction "2_2") (pintype "passive"))
      (node (ref "J2") (pin "3") (pinfunction "Pin-3_3") (pintype "power_in"))
    )
    (net (code "132") (name "VMCU") (class "Default")
      (node (ref "C108") (pin "2") (pinfunction "2_2") (pintype "passive"))
      (node (ref "C113") (pin "2") (pinfunction "2_2") (pintype "passive"))
      (node (ref "C118") (pin "2") (pinfunction "2_2") (pintype "passive"))
      (node (ref "C128") (pin "2") (pinfunction "2_2") (pintype "passive"))
      (node (ref "J2") (pin "2") (pinfunction "Pin-2_2") (pintype "power_in"))
      (node (ref "J2") (pin "59") (pinfunction "Pin-59_59") (pintype "power_in"))
      (node (ref "J3") (pin "2") (pinfunction "Pin-2_2") (pintype "power_in"))
      (node (ref "J3") (pin "59") (pinfunction "Pin-59_59") (pintype "power_in"))
    )
  )
)
